# Boost_Converter_XL6009.net
KiCad netlist of a schematic drawn in Altium Designer
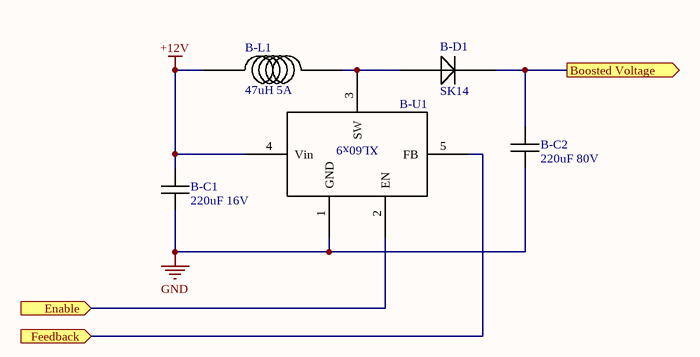
[diagram p0: Boost Converter XL6009.SchDoc]

(export (version "E")
  (design (tool "Eeschema 10.0.6"))
  (components
    (comp (ref "B-C1")
      (value "220uF 16V")
      (footprint "C 0805 / 2012")
      (libsource (lib "Standard") (part "Capacitor"))
    )
    (comp (ref "B-C2")
      (value "220uF 80V")
      (footprint "C 0805 / 2012")
      (libsource (lib "Standard") (part "Capacitor"))
    )
    (comp (ref "B-D1") (value "SK14") (libsource (lib "Standard") (part "Diode")))
    (comp (ref "B-L1") (value "47uH 5A") (libsource (lib "Standard") (part "Coil")))
    (comp (ref "B-U1")
      (value "XL6009")
      (description "Buck-/Boost-Converter")
      (libsource (lib "ICs") (part "XL60x9"))
    )
  )
  (nets
    (net (code "1") (name "+12V") (class "Default")
      (node (ref "B-C1") (pin "1") (pinfunction "1_1") (pintype "passive"))
      (node (ref "B-L1") (pin "1") (pinfunction "1_1") (pintype "passive"))
      (node (ref "B-U1") (pin "4") (pinfunction "Vin_4") (pintype "passive"))
    )
    (net (code "2") (name "/Boosted Voltage") (class "Default")
      (node (ref "B-C2") (pin "1") (pinfunction "1_1") (pintype "passive"))
      (node (ref "B-D1") (pin "1") (pinfunction "1_1") (pintype "passive"))
    )
    (net (code "3") (name "/Enable") (class "Default")
      (node (ref "B-U1") (pin "2") (pinfunction "EN_2") (pintype "passive"))
    )
    (net (code "4") (name "/Feedback") (class "Default")
      (node (ref "B-U1") (pin "5") (pinfunction "FB_5") (pintype "passive"))
    )
    (net (code "5") (name "GND") (class "Default")
      (node (ref "B-C1") (pin "2") (pinfunction "1_2") (pintype "passive"))
      (node (ref "B-C2") (pin "2") (pinfunction "1_2") (pintype "passive"))
      (node (ref "B-U1") (pin "1") (pinfunction "GND_1") (pintype "passive"))
    )
    (net (code "6") (name "Net-(B-U1-SW)") (class "Default")
      (node (ref "B-D1") (pin "2") (pinfunction "2_2") (pintype "passive"))
      (node (ref "B-L1") (pin "2") (pinfunction "2_2") (pintype "passive"))
      (node (ref "B-U1") (pin "3") (pinfunction "SW_3") (pintype "passive"))
    )
  )
)
